# ProPrj___2025-10-22.net
KiCad netlist of a schematic drawn in EasyEDA Pro
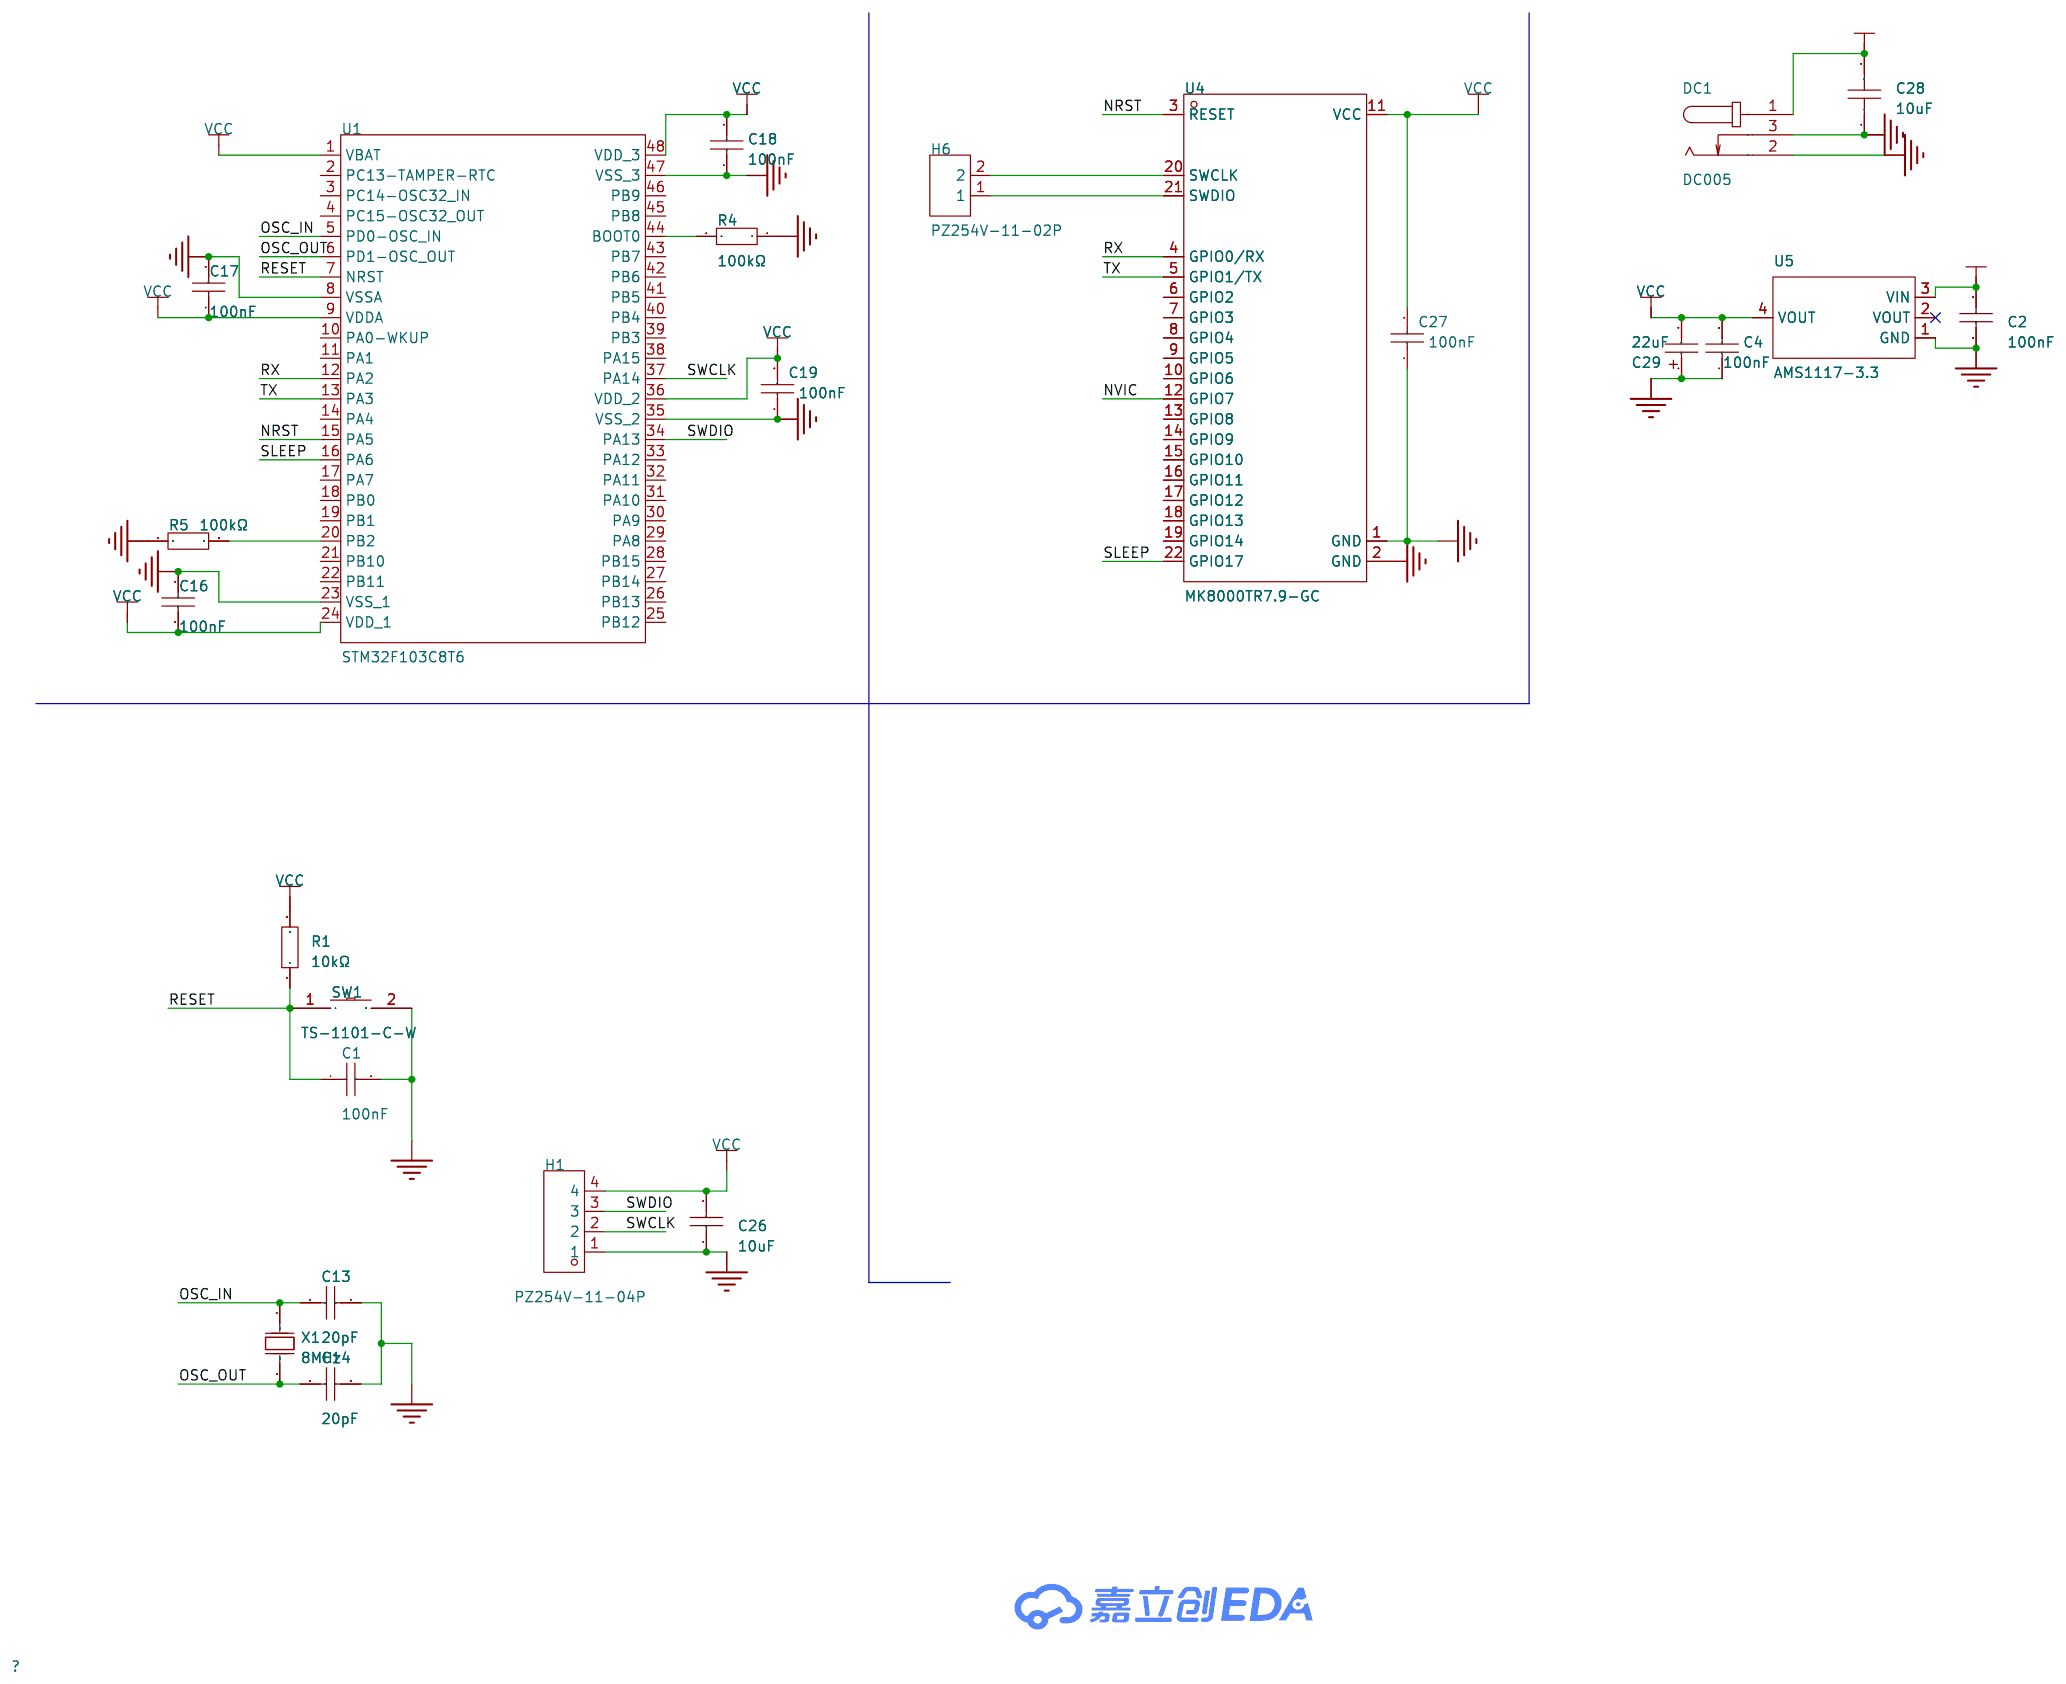
[diagram p0: schematic sheet]

(export (version "E")
  (design (tool "Eeschema 10.0.6"))
  (components
    (comp (ref "C1")
      (value "100nF")
      (footprint "easyedapro:C0805")
      (description "容值:100nF;精度:±10%;额定电压:50V;材质(温度系数):X7R;")
      (fields
        (field (name "Manufacturer Part") "CL21B104KBCNNNC")
        (field (name "Manufacturer") "SAMSUNG(三星)")
      )
      (libsource (lib "easyedapro") (part "CL21B104KBCNNNC"))
    )
    (comp (ref "C2")
      (value "100nF")
      (footprint "easyedapro:C0805")
      (description "容值:100nF;精度:±10%;额定电压:50V;材质(温度系数):X7R;")
      (fields
        (field (name "Manufacturer Part") "CL21B104KBCNNNC")
        (field (name "Manufacturer") "SAMSUNG(三星)")
      )
      (libsource (lib "easyedapro") (part "CL21B104KBCNNNC"))
    )
    (comp (ref "C4")
      (value "100nF")
      (footprint "easyedapro:C0805")
      (description "容值:100nF;精度:±10%;额定电压:50V;材质(温度系数):X7R;")
      (fields
        (field (name "Manufacturer Part") "CL21B104KBCNNNC")
        (field (name "Manufacturer") "SAMSUNG(三星)")
      )
      (libsource (lib "easyedapro") (part "CL21B104KBCNNNC"))
    )
    (comp (ref "C13")
      (value "20pF")
      (footprint "easyedapro:C0805")
      (description "容值:20pF;精度:±5%;额定电压:50V;材质(温度系数):C0G;")
      (fields
        (field (name "Manufacturer Part") "CL21C200JBANNNC")
        (field (name "Manufacturer") "SAMSUNG(三星)")
      )
      (libsource (lib "easyedapro") (part "CL21C200JBANNNC"))
    )
    (comp (ref "C14")
      (value "20pF")
      (footprint "easyedapro:C0805")
      (description "容值:20pF;精度:±5%;额定电压:50V;材质(温度系数):C0G;")
      (fields
        (field (name "Manufacturer Part") "CL21C200JBANNNC")
        (field (name "Manufacturer") "SAMSUNG(三星)")
      )
      (libsource (lib "easyedapro") (part "CL21C200JBANNNC"))
    )
    (comp (ref "C16")
      (value "100nF")
      (footprint "easyedapro:C0805")
      (description "容值:100nF;精度:±10%;额定电压:50V;材质(温度系数):X7R;")
      (fields
        (field (name "Manufacturer Part") "CL21B104KBCNNNC")
        (field (name "Manufacturer") "SAMSUNG(三星)")
      )
      (libsource (lib "easyedapro") (part "CL21B104KBCNNNC"))
    )
    (comp (ref "C17")
      (value "100nF")
      (footprint "easyedapro:C0805")
      (description "容值:100nF;精度:±10%;额定电压:50V;材质(温度系数):X7R;")
      (fields
        (field (name "Manufacturer Part") "CL21B104KBCNNNC")
        (field (name "Manufacturer") "SAMSUNG(三星)")
      )
      (libsource (lib "easyedapro") (part "CL21B104KBCNNNC"))
    )
    (comp (ref "C18")
      (value "100nF")
      (footprint "easyedapro:C0805")
      (description "容值:100nF;精度:±10%;额定电压:50V;材质(温度系数):X7R;")
      (fields
        (field (name "Manufacturer Part") "CL21B104KBCNNNC")
        (field (name "Manufacturer") "SAMSUNG(三星)")
      )
      (libsource (lib "easyedapro") (part "CL21B104KBCNNNC"))
    )
    (comp (ref "C19")
      (value "100nF")
      (footprint "easyedapro:C0805")
      (description "容值:100nF;精度:±10%;额定电压:50V;材质(温度系数):X7R;")
      (fields
        (field (name "Manufacturer Part") "CL21B104KBCNNNC")
        (field (name "Manufacturer") "SAMSUNG(三星)")
      )
      (libsource (lib "easyedapro") (part "CL21B104KBCNNNC"))
    )
    (comp (ref "C26")
      (value "10uF")
      (footprint "easyedapro:C0805")
      (description "容值:10uF;精度:±10%;额定电压:16V;温度系数:X5R;")
      (fields
        (field (name "Manufacturer Part") "CL21A106KOQNNNE")
        (field (name "Manufacturer") "SAMSUNG(三星)")
      )
      (libsource (lib "easyedapro") (part "CL21A106KOQNNNE"))
    )
    (comp (ref "C27")
      (value "100nF")
      (footprint "easyedapro:C0805")
      (description "容值:100nF;精度:±10%;额定电压:50V;材质(温度系数):X7R;")
      (fields
        (field (name "Manufacturer Part") "CL21B104KBCNNNC")
        (field (name "Manufacturer") "SAMSUNG(三星)")
      )
      (libsource (lib "easyedapro") (part "CL21B104KBCNNNC"))
    )
    (comp (ref "C28")
      (value "10uF")
      (footprint "easyedapro:C0805")
      (description "容值:10uF;精度:±10%;额定电压:50V;温度系数:X5R;")
      (fields
        (field (name "Manufacturer Part") "CL21A106KBYQNNE")
        (field (name "Manufacturer") "SAMSUNG(三星)")
      )
      (libsource (lib "easyedapro") (part "CL21A106KBYQNNE"))
    )
    (comp (ref "C29")
      (value "22uF")
      (footprint "easyedapro:CASE-A_3216")
      (description "容值:22uF;精度:±10%;额定电压:10V;等效串联电阻(ESR):3Ω@100kHz;")
      (fields (field (name "Manufacturer Part") "TAJA226K010RNJ") (field (name "Manufacturer") "Kyocera AVX"))
      (libsource (lib "easyedapro") (part "TAJA226K010RNJ"))
    )
    (comp (ref "DC1")
      (value "DC005")
      (footprint "easyedapro:DC-IN-TH_DC005")
      (description "连接器类型:DC电源插座;安装方式:弯插;触点内径:2mm;触点外径:6.3mm;额定电流:500mA;额定电压:30V;工作温度:-25°C~+70°C;")
      (fields (field (name "Manufacturer") "SHOU HAN(首韩)"))
      (libsource (lib "easyedapro") (part "DC005_C431533"))
    )
    (comp (ref "H1")
      (value "PZ254V-11-04P")
      (footprint "easyedapro:HDR-TH_4P-P2.54-V-M")
      (fields (field (name "Manufacturer") "XFCN(兴飞)"))
      (libsource (lib "easyedapro") (part "PZ254V-11-04P_C2691448"))
    )
    (comp (ref "H6")
      (value "PZ254V-11-02P")
      (footprint "easyedapro:HDR-TH_2P-P2.54-V-M")
      (fields (field (name "Manufacturer") "XFCN(兴飞)"))
      (libsource (lib "easyedapro") (part "PZ254V-11-02P"))
    )
    (comp (ref "R1")
      (value "10kΩ")
      (footprint "easyedapro:R0805")
      (description "电阻类型:厚膜电阻;阻值:10kΩ;精度:±1%;功率:125mW;工作电压:150V;温度系数:±100ppm/°C;")
      (fields
        (field (name "Manufacturer Part") "0805W8F1002T5E")
        (field (name "Manufacturer") "UNI-ROYAL(厚声)")
      )
      (libsource (lib "easyedapro") (part "0805W8F1002T5E"))
    )
    (comp (ref "R4")
      (value "100kΩ")
      (footprint "easyedapro:R0805")
      (description "电阻类型:厚膜电阻;阻值:100kΩ;精度:±1%;功率:125mW;工作电压:150V;温度系数:±100ppm/°C;")
      (fields
        (field (name "Manufacturer Part") "0805W8F1003T5E")
        (field (name "Manufacturer") "UNI-ROYAL(厚声)")
      )
      (libsource (lib "easyedapro") (part "0805W8F1003T5E_C149504"))
    )
    (comp (ref "R5")
      (value "100kΩ")
      (footprint "easyedapro:R0805")
      (description "电阻类型:厚膜电阻;阻值:100kΩ;精度:±1%;功率:125mW;工作电压:150V;温度系数:±100ppm/°C;")
      (fields
        (field (name "Manufacturer Part") "0805W8F1003T5E")
        (field (name "Manufacturer") "UNI-ROYAL(厚声)")
      )
      (libsource (lib "easyedapro") (part "0805W8F1003T5E_C149504"))
    )
    (comp (ref "SW1")
      (value "TS-1101-C-W")
      (footprint "easyedapro:SW-SMD_L6.0-W3.3-LS8.0")
      (fields (field (name "Manufacturer") "XKB Connectivity(中国星坤)"))
      (libsource (lib "easyedapro") (part "TS-1101-C-W"))
    )
    (comp (ref "U1")
      (value "STM32F103C8T6")
      (footprint "easyedapro:LQFP-48_L7.0-W7.0-P0.50-LS9.0-BL")
      (description "CPU内核:ARM-M3;CPU最大主频:72MHz;应用领域:-;")
      (fields (field (name "Manufacturer") "ST(意法半导体)"))
      (libsource (lib "easyedapro") (part "STM32F103C8T6"))
    )
    (comp (ref "U4")
      (value "MK8000TR7.9-GC")
      (footprint "easyedapro:COMM-SMD_L26.3-W16.1_MK8000TR7.9-GC")
      (description "国产UWB测距模块电子围栏应用")
      (fields (field (name "Manufacturer") "Silicontra(硅传科技)"))
      (libsource (lib "easyedapro") (part "MK8000TR7.9-GC"))
    )
    (comp (ref "U5")
      (value "AMS1117-3.3")
      (footprint "easyedapro:SOT-223-3_L6.5-W3.4-P2.30-LS7.0-BR")
      (description "输出类型:固定;工作电压:16V;输出电压:3.3V;输出电流:1A;电源纹波抑制比(PSRR):72dB@(120Hz);输出极性:正极;")
      (fields (field (name "Manufacturer") "AMS"))
      (libsource (lib "easyedapro") (part "AMS1117-3.3"))
    )
    (comp (ref "X1")
      (value "8MHz")
      (footprint "easyedapro:CRYSTAL-SMD_L11.5-W4.8-LS12.7")
      (description "晶振类型:贴片晶振;频率:8MHz;常温频差:±20ppm;负载电容:20pF;频率稳定度:±30ppm;")
      (fields (field (name "Manufacturer Part") "X49SM8MSD2SC") (field (name "Manufacturer") "YXC(扬兴晶振)"))
      (libsource (lib "easyedapro") (part "X49SM8MSD2SC"))
    )
  )
  (nets
    (net (code "1") (name "+12V") (class "Default")
      (node (ref "C2") (pin "2") (pinfunction "2_2") (pintype "input"))
      (node (ref "C28") (pin "2") (pinfunction "2_2") (pintype "unspecified"))
      (node (ref "DC1") (pin "1") (pinfunction "1_1") (pintype "unspecified"))
      (node (ref "U5") (pin "3") (pinfunction "VIN_3") (pintype "unspecified"))
    )
    (net (code "2") (name "/NRST") (class "Default")
      (node (ref "U1") (pin "15") (pinfunction "PA5_15") (pintype "unspecified"))
      (node (ref "U4") (pin "3") (pinfunction "RESET_3") (pintype "unspecified"))
    )
    (net (code "3") (name "/NVIC") (class "Default")
      (node (ref "U4") (pin "12") (pinfunction "GPIO7_12") (pintype "unspecified"))
    )
    (net (code "4") (name "/OSC_IN") (class "Default")
      (node (ref "C13") (pin "2") (pinfunction "2_2") (pintype "input"))
      (node (ref "U1") (pin "5") (pinfunction "PD0-OSC_IN_5") (pintype "unspecified"))
      (node (ref "X1") (pin "1") (pinfunction "OSC1_1") (pintype "input"))
    )
    (net (code "5") (name "/OSC_OUT") (class "Default")
      (node (ref "C14") (pin "2") (pinfunction "2_2") (pintype "input"))
      (node (ref "U1") (pin "6") (pinfunction "PD1-OSC_OUT_6") (pintype "unspecified"))
      (node (ref "X1") (pin "2") (pinfunction "OSC2_2") (pintype "input"))
    )
    (net (code "6") (name "/RESET") (class "Default")
      (node (ref "C1") (pin "1") (pinfunction "1_1") (pintype "input"))
      (node (ref "R1") (pin "1") (pinfunction "1_1") (pintype "input"))
      (node (ref "SW1") (pin "1") (pinfunction "1_1") (pintype "unspecified"))
      (node (ref "U1") (pin "7") (pinfunction "NRST_7") (pintype "unspecified"))
    )
    (net (code "7") (name "/RX") (class "Default")
      (node (ref "U1") (pin "12") (pinfunction "PA2_12") (pintype "unspecified"))
      (node (ref "U4") (pin "4") (pinfunction "GPIO0/RX_4") (pintype "unspecified"))
    )
    (net (code "8") (name "/SLEEP") (class "Default")
      (node (ref "U1") (pin "16") (pinfunction "PA6_16") (pintype "unspecified"))
      (node (ref "U4") (pin "22") (pinfunction "GPIO17_22") (pintype "unspecified"))
    )
    (net (code "9") (name "/SWCLK") (class "Default")
      (node (ref "H1") (pin "2") (pinfunction "2_2") (pintype "unspecified"))
      (node (ref "U1") (pin "37") (pinfunction "PA14_37") (pintype "unspecified"))
    )
    (net (code "10") (name "/SWDIO") (class "Default")
      (node (ref "H1") (pin "3") (pinfunction "3_3") (pintype "unspecified"))
      (node (ref "U1") (pin "34") (pinfunction "PA13_34") (pintype "unspecified"))
    )
    (net (code "11") (name "/TX") (class "Default")
      (node (ref "U1") (pin "13") (pinfunction "PA3_13") (pintype "unspecified"))
      (node (ref "U4") (pin "5") (pinfunction "GPIO1/TX_5") (pintype "unspecified"))
    )
    (net (code "12") (name "GND") (class "Default")
      (node (ref "C1") (pin "2") (pinfunction "2_2") (pintype "input"))
      (node (ref "C13") (pin "1") (pinfunction "1_1") (pintype "input"))
      (node (ref "C14") (pin "1") (pinfunction "1_1") (pintype "input"))
      (node (ref "C16") (pin "1") (pinfunction "1_1") (pintype "input"))
      (node (ref "C17") (pin "2") (pinfunction "2_2") (pintype "input"))
      (node (ref "C18") (pin "1") (pinfunction "1_1") (pintype "input"))
      (node (ref "C19") (pin "1") (pinfunction "1_1") (pintype "input"))
      (node (ref "C2") (pin "1") (pinfunction "1_1") (pintype "input"))
      (node (ref "C26") (pin "1") (pinfunction "1_1") (pintype "input"))
      (node (ref "C27") (pin "1") (pinfunction "1_1") (pintype "input"))
      (node (ref "C28") (pin "1") (pinfunction "1_1") (pintype "unspecified"))
      (node (ref "C29") (pin "1") (pinfunction "1_1") (pintype "input"))
      (node (ref "C4") (pin "1") (pinfunction "1_1") (pintype "input"))
      (node (ref "DC1") (pin "2") (pinfunction "2_2") (pintype "unspecified"))
      (node (ref "DC1") (pin "3") (pinfunction "3_3") (pintype "unspecified"))
      (node (ref "H1") (pin "1") (pinfunction "1_1") (pintype "unspecified"))
      (node (ref "R4") (pin "1") (pinfunction "1_1") (pintype "unspecified"))
      (node (ref "R5") (pin "1") (pinfunction "1_1") (pintype "unspecified"))
      (node (ref "SW1") (pin "2") (pinfunction "2_2") (pintype "unspecified"))
      (node (ref "U1") (pin "23") (pinfunction "VSS_1_23") (pintype "unspecified"))
      (node (ref "U1") (pin "35") (pinfunction "VSS_2_35") (pintype "unspecified"))
      (node (ref "U1") (pin "47") (pinfunction "VSS_3_47") (pintype "unspecified"))
      (node (ref "U1") (pin "8") (pinfunction "VSSA_8") (pintype "unspecified"))
      (node (ref "U4") (pin "1") (pinfunction "GND_1") (pintype "unspecified"))
      (node (ref "U4") (pin "2") (pinfunction "GND_2") (pintype "unspecified"))
      (node (ref "U5") (pin "1") (pinfunction "GND_1") (pintype "unspecified"))
    )
    (net (code "13") (name "Net-(U1-BOOT0)") (class "Default")
      (node (ref "R4") (pin "2") (pinfunction "2_2") (pintype "unspecified"))
      (node (ref "U1") (pin "44") (pinfunction "BOOT0_44") (pintype "unspecified"))
    )
    (net (code "14") (name "Net-(U1-PB2)") (class "Default")
      (node (ref "R5") (pin "2") (pinfunction "2_2") (pintype "unspecified"))
      (node (ref "U1") (pin "20") (pinfunction "PB2_20") (pintype "unspecified"))
    )
    (net (code "15") (name "Net-(U4-SWCLK)") (class "Default")
      (node (ref "H6") (pin "2") (pinfunction "2_2") (pintype "unspecified"))
      (node (ref "U4") (pin "20") (pinfunction "SWCLK_20") (pintype "unspecified"))
    )
    (net (code "16") (name "Net-(U4-SWDIO)") (class "Default")
      (node (ref "H6") (pin "1") (pinfunction "1_1") (pintype "unspecified"))
      (node (ref "U4") (pin "21") (pinfunction "SWDIO_21") (pintype "unspecified"))
    )
    (net (code "17") (name "VCC") (class "Default")
      (node (ref "C16") (pin "2") (pinfunction "2_2") (pintype "input"))
      (node (ref "C17") (pin "1") (pinfunction "1_1") (pintype "input"))
      (node (ref "C18") (pin "2") (pinfunction "2_2") (pintype "input"))
      (node (ref "C19") (pin "2") (pinfunction "2_2") (pintype "input"))
      (node (ref "C26") (pin "2") (pinfunction "2_2") (pintype "input"))
      (node (ref "C27") (pin "2") (pinfunction "2_2") (pintype "input"))
      (node (ref "C29") (pin "2") (pinfunction "2_2") (pintype "input"))
      (node (ref "C4") (pin "2") (pinfunction "2_2") (pintype "input"))
      (node (ref "H1") (pin "4") (pinfunction "4_4") (pintype "unspecified"))
      (node (ref "R1") (pin "2") (pinfunction "2_2") (pintype "input"))
      (node (ref "U1") (pin "1") (pinfunction "VBAT_1") (pintype "unspecified"))
      (node (ref "U1") (pin "24") (pinfunction "VDD_1_24") (pintype "unspecified"))
      (node (ref "U1") (pin "36") (pinfunction "VDD_2_36") (pintype "unspecified"))
      (node (ref "U1") (pin "48") (pinfunction "VDD_3_48") (pintype "unspecified"))
      (node (ref "U1") (pin "9") (pinfunction "VDDA_9") (pintype "unspecified"))
      (node (ref "U4") (pin "11") (pinfunction "VCC_11") (pintype "unspecified"))
      (node (ref "U5") (pin "4") (pinfunction "VOUT_4") (pintype "unspecified"))
    )
    (net (code "18") (name "unconnected-(U1-PA0-WKUP-Pad10)") (class "Default")
      (node (ref "U1") (pin "10") (pinfunction "PA0-WKUP_10") (pintype "unspecified"))
    )
    (net (code "19") (name "unconnected-(U1-PA1-Pad11)") (class "Default")
      (node (ref "U1") (pin "11") (pinfunction "PA1_11") (pintype "unspecified"))
    )
    (net (code "20") (name "unconnected-(U1-PA4-Pad14)") (class "Default")
      (node (ref "U1") (pin "14") (pinfunction "PA4_14") (pintype "unspecified"))
    )
    (net (code "21") (name "unconnected-(U1-PA7-Pad17)") (class "Default")
      (node (ref "U1") (pin "17") (pinfunction "PA7_17") (pintype "unspecified"))
    )
    (net (code "22") (name "unconnected-(U1-PA8-Pad29)") (class "Default")
      (node (ref "U1") (pin "29") (pinfunction "PA8_29") (pintype "unspecified"))
    )
    (net (code "23") (name "unconnected-(U1-PA9-Pad30)") (class "Default")
      (node (ref "U1") (pin "30") (pinfunction "PA9_30") (pintype "unspecified"))
    )
    (net (code "24") (name "unconnected-(U1-PA10-Pad31)") (class "Default")
      (node (ref "U1") (pin "31") (pinfunction "PA10_31") (pintype "unspecified"))
    )
    (net (code "25") (name "unconnected-(U1-PA11-Pad32)") (class "Default")
      (node (ref "U1") (pin "32") (pinfunction "PA11_32") (pintype "unspecified"))
    )
    (net (code "26") (name "unconnected-(U1-PA12-Pad33)") (class "Default")
      (node (ref "U1") (pin "33") (pinfunction "PA12_33") (pintype "unspecified"))
    )
    (net (code "27") (name "unconnected-(U1-PA15-Pad38)") (class "Default")
      (node (ref "U1") (pin "38") (pinfunction "PA15_38") (pintype "unspecified"))
    )
    (net (code "28") (name "unconnected-(U1-PB0-Pad18)") (class "Default")
      (node (ref "U1") (pin "18") (pinfunction "PB0_18") (pintype "unspecified"))
    )
    (net (code "29") (name "unconnected-(U1-PB1-Pad19)") (class "Default")
      (node (ref "U1") (pin "19") (pinfunction "PB1_19") (pintype "unspecified"))
    )
    (net (code "30") (name "unconnected-(U1-PB3-Pad39)") (class "Default")
      (node (ref "U1") (pin "39") (pinfunction "PB3_39") (pintype "unspecified"))
    )
    (net (code "31") (name "unconnected-(U1-PB4-Pad40)") (class "Default")
      (node (ref "U1") (pin "40") (pinfunction "PB4_40") (pintype "unspecified"))
    )
    (net (code "32") (name "unconnected-(U1-PB5-Pad41)") (class "Default")
      (node (ref "U1") (pin "41") (pinfunction "PB5_41") (pintype "unspecified"))
    )
    (net (code "33") (name "unconnected-(U1-PB6-Pad42)") (class "Default")
      (node (ref "U1") (pin "42") (pinfunction "PB6_42") (pintype "unspecified"))
    )
    (net (code "34") (name "unconnected-(U1-PB7-Pad43)") (class "Default")
      (node (ref "U1") (pin "43") (pinfunction "PB7_43") (pintype "unspecified"))
    )
    (net (code "35") (name "unconnected-(U1-PB8-Pad45)") (class "Default")
      (node (ref "U1") (pin "45") (pinfunction "PB8_45") (pintype "unspecified"))
    )
    (net (code "36") (name "unconnected-(U1-PB9-Pad46)") (class "Default")
      (node (ref "U1") (pin "46") (pinfunction "PB9_46") (pintype "unspecified"))
    )
    (net (code "37") (name "unconnected-(U1-PB10-Pad21)") (class "Default")
      (node (ref "U1") (pin "21") (pinfunction "PB10_21") (pintype "unspecified"))
    )
    (net (code "38") (name "unconnected-(U1-PB11-Pad22)") (class "Default")
      (node (ref "U1") (pin "22") (pinfunction "PB11_22") (pintype "unspecified"))
    )
    (net (code "39") (name "unconnected-(U1-PB12-Pad25)") (class "Default")
      (node (ref "U1") (pin "25") (pinfunction "PB12_25") (pintype "unspecified"))
    )
    (net (code "40") (name "unconnected-(U1-PB13-Pad26)") (class "Default")
      (node (ref "U1") (pin "26") (pinfunction "PB13_26") (pintype "unspecified"))
    )
    (net (code "41") (name "unconnected-(U1-PB14-Pad27)") (class "Default")
      (node (ref "U1") (pin "27") (pinfunction "PB14_27") (pintype "unspecified"))
    )
    (net (code "42") (name "unconnected-(U1-PB15-Pad28)") (class "Default")
      (node (ref "U1") (pin "28") (pinfunction "PB15_28") (pintype "unspecified"))
    )
    (net (code "43") (name "unconnected-(U1-PC13-TAMPER-RTC-Pad2)") (class "Default")
      (node (ref "U1") (pin "2") (pinfunction "PC13-TAMPER-RTC_2") (pintype "unspecified"))
    )
    (net (code "44") (name "unconnected-(U1-PC14-OSC32_IN-Pad3)") (class "Default")
      (node (ref "U1") (pin "3") (pinfunction "PC14-OSC32_IN_3") (pintype "unspecified"))
    )
    (net (code "45") (name "unconnected-(U1-PC15-OSC32_OUT-Pad4)") (class "Default")
      (node (ref "U1") (pin "4") (pinfunction "PC15-OSC32_OUT_4") (pintype "unspecified"))
    )
    (net (code "46") (name "unconnected-(U4-GPIO2-Pad6)") (class "Default")
      (node (ref "U4") (pin "6") (pinfunction "GPIO2_6") (pintype "unspecified"))
    )
    (net (code "47") (name "unconnected-(U4-GPIO3-Pad7)") (class "Default")
      (node (ref "U4") (pin "7") (pinfunction "GPIO3_7") (pintype "unspecified"))
    )
    (net (code "48") (name "unconnected-(U4-GPIO4-Pad8)") (class "Default")
      (node (ref "U4") (pin "8") (pinfunction "GPIO4_8") (pintype "unspecified"))
    )
    (net (code "49") (name "unconnected-(U4-GPIO5-Pad9)") (class "Default")
      (node (ref "U4") (pin "9") (pinfunction "GPIO5_9") (pintype "unspecified"))
    )
    (net (code "50") (name "unconnected-(U4-GPIO6-Pad10)") (class "Default")
      (node (ref "U4") (pin "10") (pinfunction "GPIO6_10") (pintype "unspecified"))
    )
    (net (code "51") (name "unconnected-(U4-GPIO8-Pad13)") (class "Default")
      (node (ref "U4") (pin "13") (pinfunction "GPIO8_13") (pintype "unspecified"))
    )
    (net (code "52") (name "unconnected-(U4-GPIO9-Pad14)") (class "Default")
      (node (ref "U4") (pin "14") (pinfunction "GPIO9_14") (pintype "unspecified"))
    )
    (net (code "53") (name "unconnected-(U4-GPIO10-Pad15)") (class "Default")
      (node (ref "U4") (pin "15") (pinfunction "GPIO10_15") (pintype "unspecified"))
    )
    (net (code "54") (name "unconnected-(U4-GPIO11-Pad16)") (class "Default")
      (node (ref "U4") (pin "16") (pinfunction "GPIO11_16") (pintype "unspecified"))
    )
    (net (code "55") (name "unconnected-(U4-GPIO12-Pad17)") (class "Default")
      (node (ref "U4") (pin "17") (pinfunction "GPIO12_17") (pintype "unspecified"))
    )
    (net (code "56") (name "unconnected-(U4-GPIO13-Pad18)") (class "Default")
      (node (ref "U4") (pin "18") (pinfunction "GPIO13_18") (pintype "unspecified"))
    )
    (net (code "57") (name "unconnected-(U4-GPIO14-Pad19)") (class "Default")
      (node (ref "U4") (pin "19") (pinfunction "GPIO14_19") (pintype "unspecified"))
    )
    (net (code "58") (name "unconnected-(U5-VOUT-Pad2)") (class "Default")
      (node (ref "U5") (pin "2") (pinfunction "VOUT_2") (pintype "unspecified+no_connect"))
    )
  )
)
